# SCH_lonsonho-switch-1.net
KiCad netlist of a schematic drawn in EasyEDA
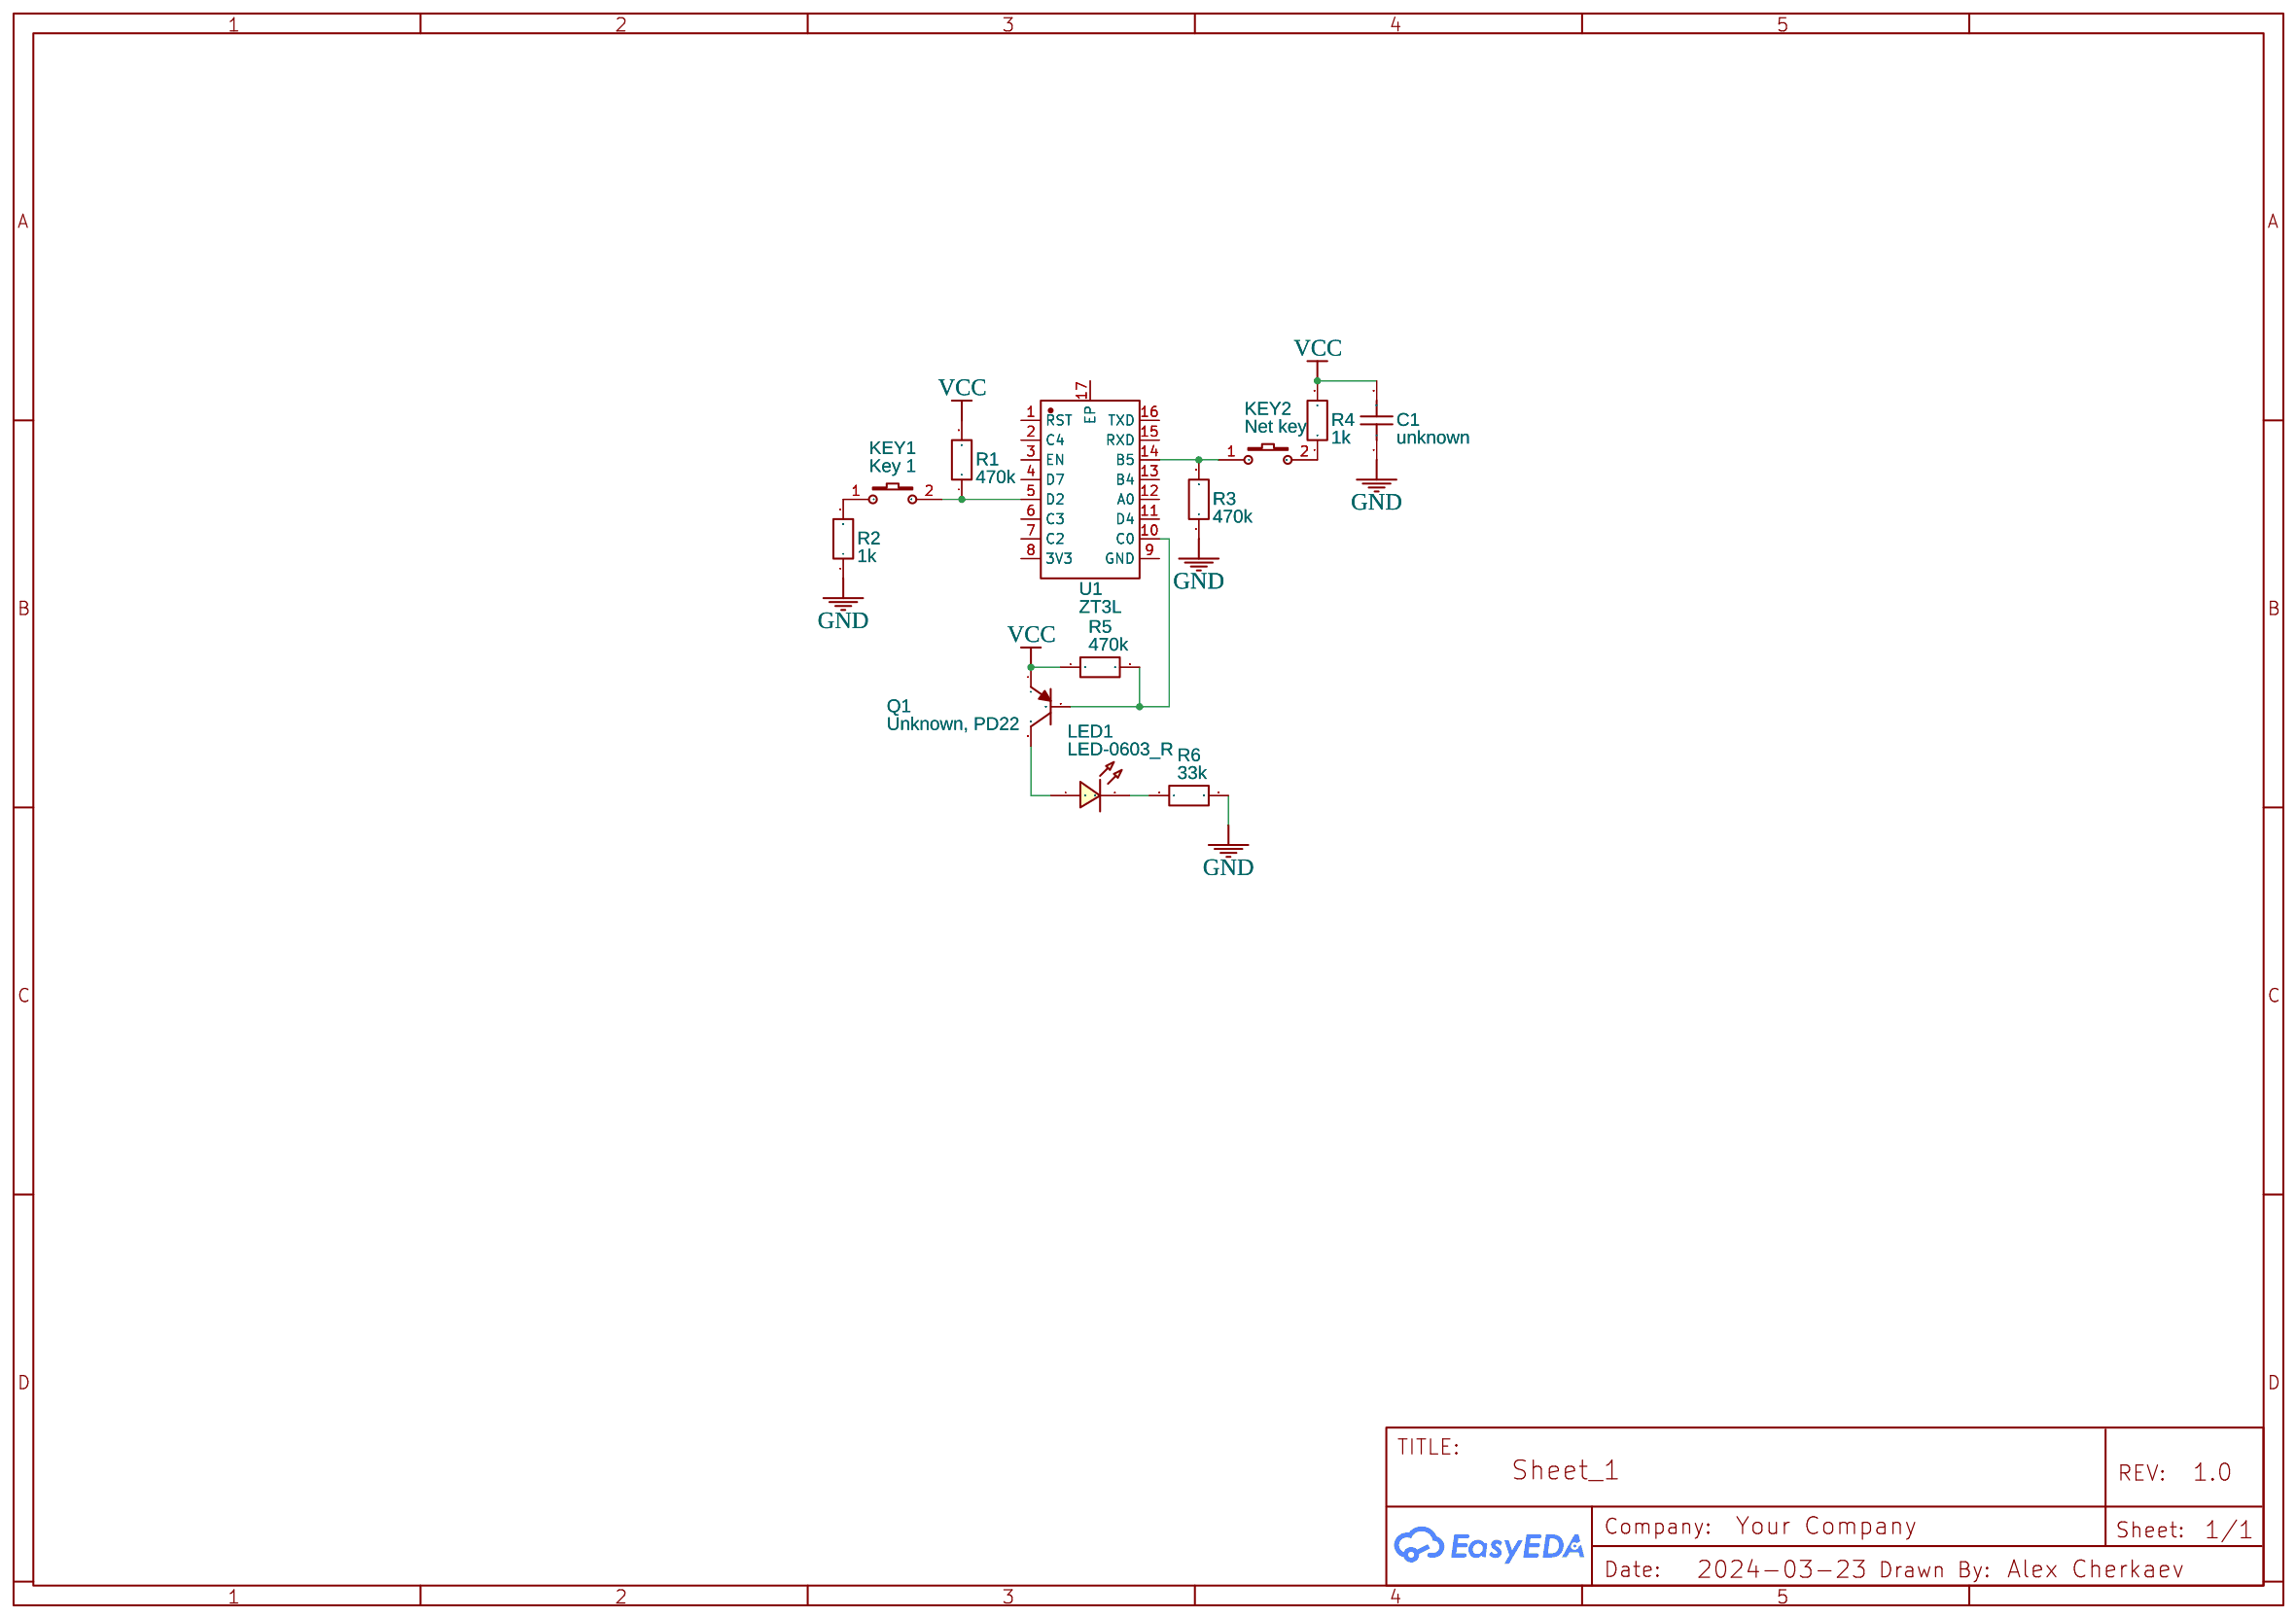
[diagram p0: schematic sheet]

(export (version "E")
  (design (tool "Eeschema 10.0.6"))
  (components
    (comp (ref "C1") (value "unknown") (libsource (lib "") (part "C_0603_US")))
    (comp (ref "KEY1")
      (value "Key 1")
      (fields (field (name "Manufacturer Part") "K2-1107ST-A4SW-06"))
      (libsource (lib "") (part "K2-3.6×6.1_SMD"))
    )
    (comp (ref "KEY2")
      (value "Net key")
      (fields (field (name "Manufacturer Part") "K2-1107ST-A4SW-06"))
      (libsource (lib "") (part "K2-3.6×6.1_SMD"))
    )
    (comp (ref "LED1")
      (value "LED-0603_R")
      (fields
        (field (name "Manufacturer Part") "19-217/R6C-AL1M2VY/3T")
        (field (name "Manufacturer") "EVERLIGHT(台湾亿光)")
      )
      (libsource (lib "") (part "LED-0603_R"))
    )
    (comp (ref "Q1")
      (value "Unknown, PD22")
      (fields (field (name "Manufacturer Part") "2N3906S-RTK/PS") (field (name "Manufacturer") "KEC"))
      (libsource (lib "") (part "2N3906(SOT-23)"))
    )
    (comp (ref "R1") (value "470k") (libsource (lib "") (part "R_0603_EU")))
    (comp (ref "R2") (value "1k") (libsource (lib "") (part "R_0603_EU")))
    (comp (ref "R3") (value "470k") (libsource (lib "") (part "R_0603_EU")))
    (comp (ref "R4") (value "1k") (libsource (lib "") (part "R_0603_EU")))
    (comp (ref "R5") (value "470k") (libsource (lib "") (part "R_0603_EU_1")))
    (comp (ref "R6") (value "33k") (libsource (lib "") (part "R_0603_EU_1")))
    (comp (ref "U1")
      (value "ZT3L")
      (fields (field (name "Manufacturer") "YTL(亚特联)"))
      (libsource (lib "") (part "ZT3L"))
    )
  )
  (nets
    (net (code "1") (name "GND") (class "Default")
      (node (ref "C1") (pin "1") (pinfunction "1_1") (pintype "unspecified"))
      (node (ref "R2") (pin "1") (pinfunction "1_1") (pintype "unspecified"))
      (node (ref "R3") (pin "1") (pinfunction "1_1") (pintype "unspecified"))
      (node (ref "R6") (pin "2") (pinfunction "2_2") (pintype "unspecified"))
    )
    (net (code "2") (name "Net-(KEY1-Pad1)") (class "Default")
      (node (ref "KEY1") (pin "1") (pinfunction "1_1") (pintype "unspecified"))
      (node (ref "R2") (pin "2") (pinfunction "2_2") (pintype "unspecified"))
    )
    (net (code "3") (name "Net-(KEY2-Pad2)") (class "Default")
      (node (ref "KEY2") (pin "2") (pinfunction "2_2") (pintype "unspecified"))
      (node (ref "R4") (pin "1") (pinfunction "1_1") (pintype "unspecified"))
    )
    (net (code "4") (name "Net-(LED1-Pad2)") (class "Default")
      (node (ref "LED1") (pin "2") (pinfunction "2_2") (pintype "unspecified"))
      (node (ref "R6") (pin "1") (pinfunction "1_1") (pintype "unspecified"))
    )
    (net (code "5") (name "Net-(Q1-B)") (class "Default")
      (node (ref "Q1") (pin "2") (pinfunction "B_2") (pintype "input"))
      (node (ref "R5") (pin "2") (pinfunction "2_2") (pintype "unspecified"))
      (node (ref "U1") (pin "10") (pinfunction "C0_10") (pintype "unspecified"))
    )
    (net (code "6") (name "Net-(Q1-C)") (class "Default")
      (node (ref "LED1") (pin "1") (pinfunction "1_1") (pintype "unspecified"))
      (node (ref "Q1") (pin "3") (pinfunction "C_3") (pintype "input"))
    )
    (net (code "7") (name "Net-(U1-B5)") (class "Default")
      (node (ref "KEY2") (pin "1") (pinfunction "1_1") (pintype "unspecified"))
      (node (ref "R3") (pin "2") (pinfunction "2_2") (pintype "unspecified"))
      (node (ref "U1") (pin "14") (pinfunction "B5_14") (pintype "unspecified"))
    )
    (net (code "8") (name "Net-(U1-D2)") (class "Default")
      (node (ref "KEY1") (pin "2") (pinfunction "2_2") (pintype "unspecified"))
      (node (ref "R1") (pin "1") (pinfunction "1_1") (pintype "unspecified"))
      (node (ref "U1") (pin "5") (pinfunction "D2_5") (pintype "unspecified"))
    )
    (net (code "9") (name "VCC") (class "Default")
      (node (ref "C1") (pin "2") (pinfunction "2_2") (pintype "unspecified"))
      (node (ref "Q1") (pin "1") (pinfunction "E_1") (pintype "input"))
      (node (ref "R1") (pin "2") (pinfunction "2_2") (pintype "unspecified"))
      (node (ref "R4") (pin "2") (pinfunction "2_2") (pintype "unspecified"))
      (node (ref "R5") (pin "1") (pinfunction "1_1") (pintype "unspecified"))
    )
    (net (code "10") (name "unconnected-(U1-3V3-Pad8)") (class "Default")
      (node (ref "U1") (pin "8") (pinfunction "3V3_8") (pintype "unspecified"))
    )
    (net (code "11") (name "unconnected-(U1-A0-Pad12)") (class "Default")
      (node (ref "U1") (pin "12") (pinfunction "A0_12") (pintype "unspecified"))
    )
    (net (code "12") (name "unconnected-(U1-B4-Pad13)") (class "Default")
      (node (ref "U1") (pin "13") (pinfunction "B4_13") (pintype "unspecified"))
    )
    (net (code "13") (name "unconnected-(U1-C2-Pad7)") (class "Default")
      (node (ref "U1") (pin "7") (pinfunction "C2_7") (pintype "unspecified"))
    )
    (net (code "14") (name "unconnected-(U1-C3-Pad6)") (class "Default")
      (node (ref "U1") (pin "6") (pinfunction "C3_6") (pintype "unspecified"))
    )
    (net (code "15") (name "unconnected-(U1-C4-Pad2)") (class "Default")
      (node (ref "U1") (pin "2") (pinfunction "C4_2") (pintype "unspecified"))
    )
    (net (code "16") (name "unconnected-(U1-D4-Pad11)") (class "Default")
      (node (ref "U1") (pin "11") (pinfunction "D4_11") (pintype "unspecified"))
    )
    (net (code "17") (name "unconnected-(U1-D7-Pad4)") (class "Default")
      (node (ref "U1") (pin "4") (pinfunction "D7_4") (pintype "unspecified"))
    )
    (net (code "18") (name "unconnected-(U1-EN-Pad3)") (class "Default")
      (node (ref "U1") (pin "3") (pinfunction "EN_3") (pintype "unspecified"))
    )
    (net (code "19") (name "unconnected-(U1-EP-Pad17)") (class "Default")
      (node (ref "U1") (pin "17") (pinfunction "EP_17") (pintype "unspecified"))
    )
    (net (code "20") (name "unconnected-(U1-GND-Pad9)") (class "Default")
      (node (ref "U1") (pin "9") (pinfunction "GND_9") (pintype "unspecified"))
    )
    (net (code "21") (name "unconnected-(U1-RST-Pad1)") (class "Default")
      (node (ref "U1") (pin "1") (pinfunction "RST_1") (pintype "unspecified"))
    )
    (net (code "22") (name "unconnected-(U1-RXD-Pad15)") (class "Default")
      (node (ref "U1") (pin "15") (pinfunction "RXD_15") (pintype "unspecified"))
    )
    (net (code "23") (name "unconnected-(U1-TXD-Pad16)") (class "Default")
      (node (ref "U1") (pin "16") (pinfunction "TXD_16") (pintype "unspecified"))
    )
  )
)
